# PQ60_CB_FV2.net
KiCad netlist of a schematic drawn in EAGLE
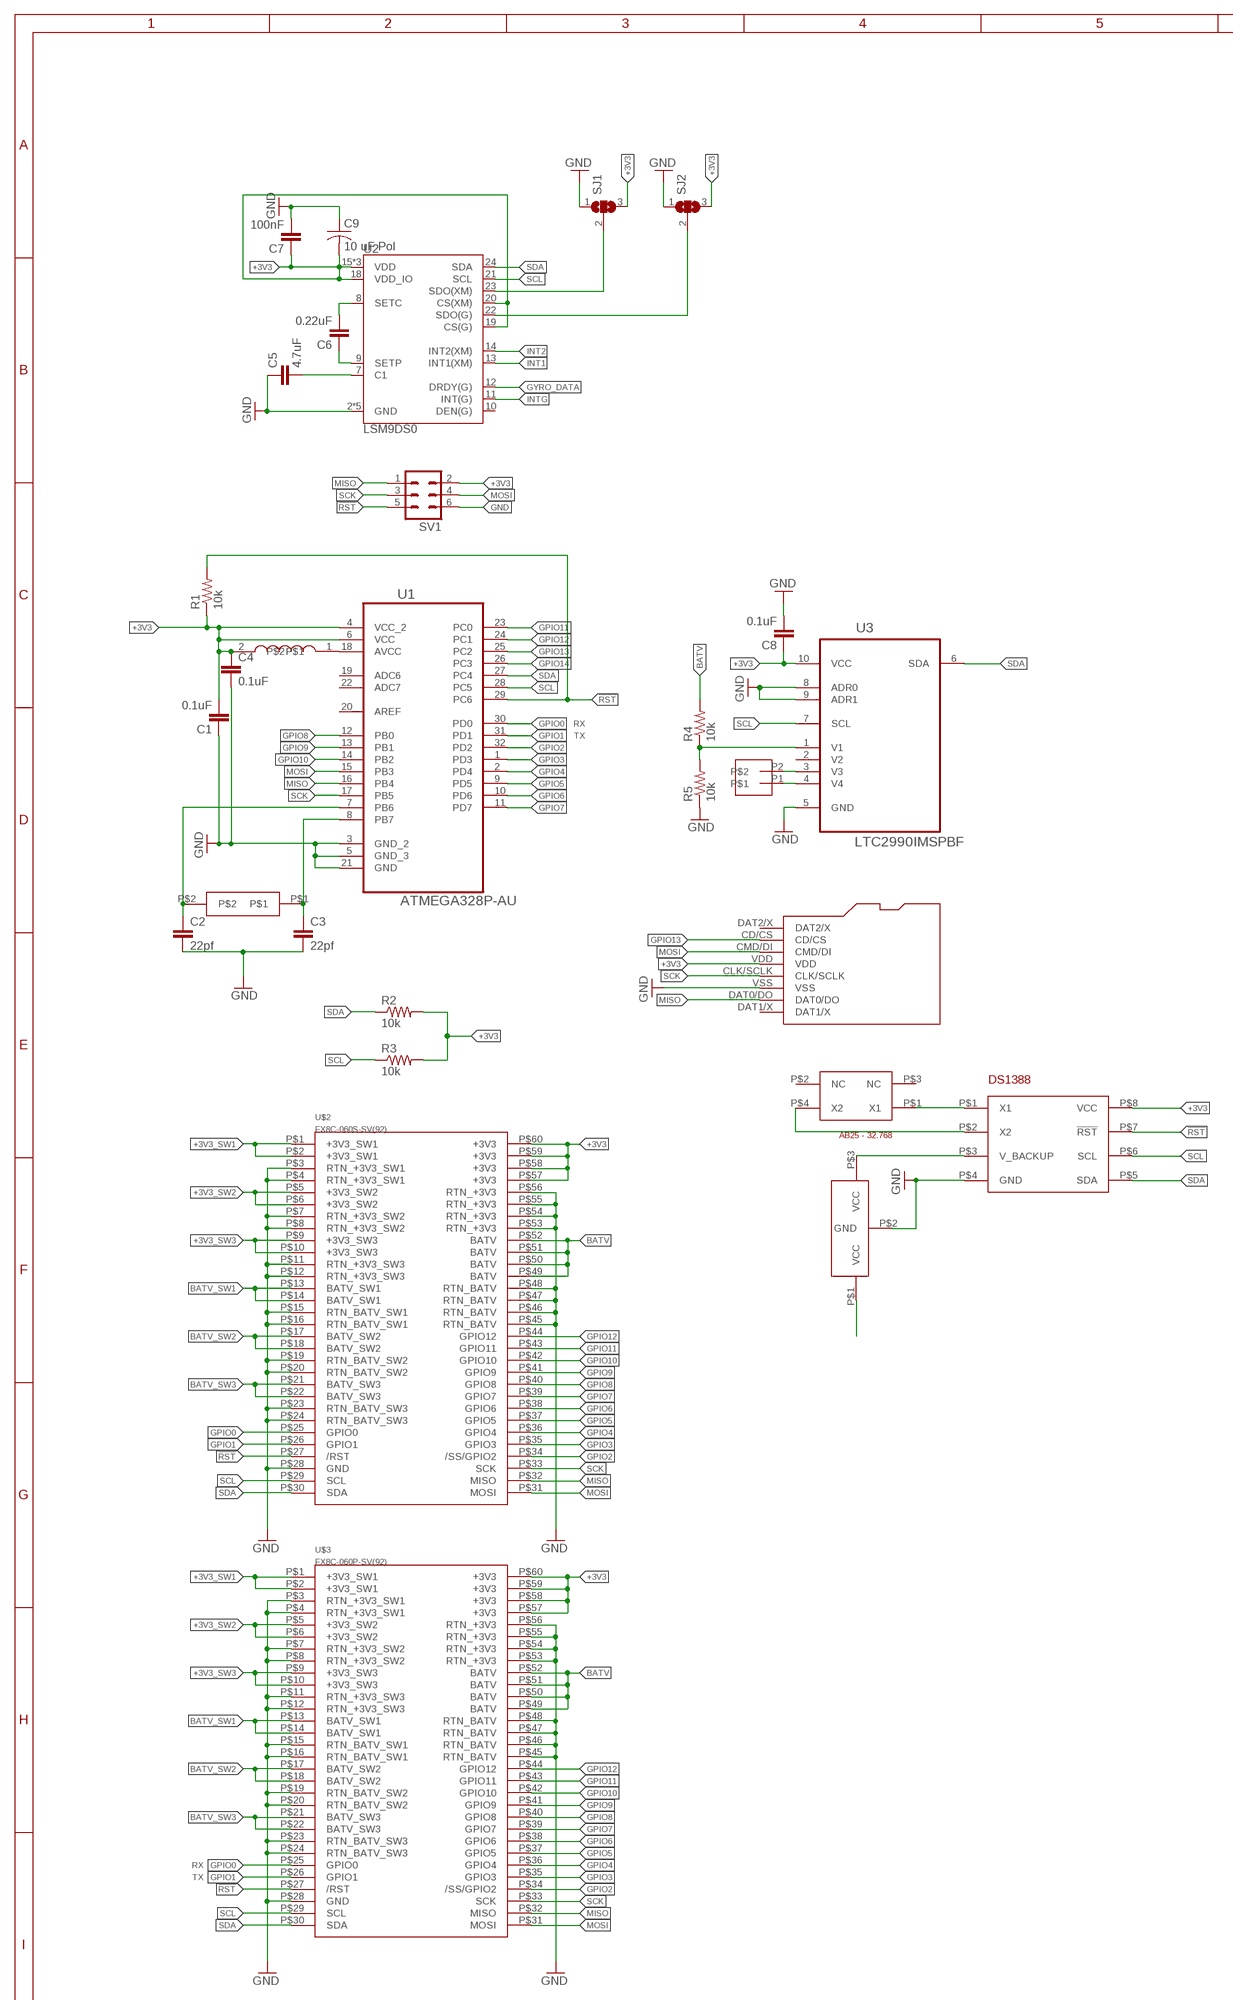
[diagram p0: schematic, sheet 1, part 1 of 2]
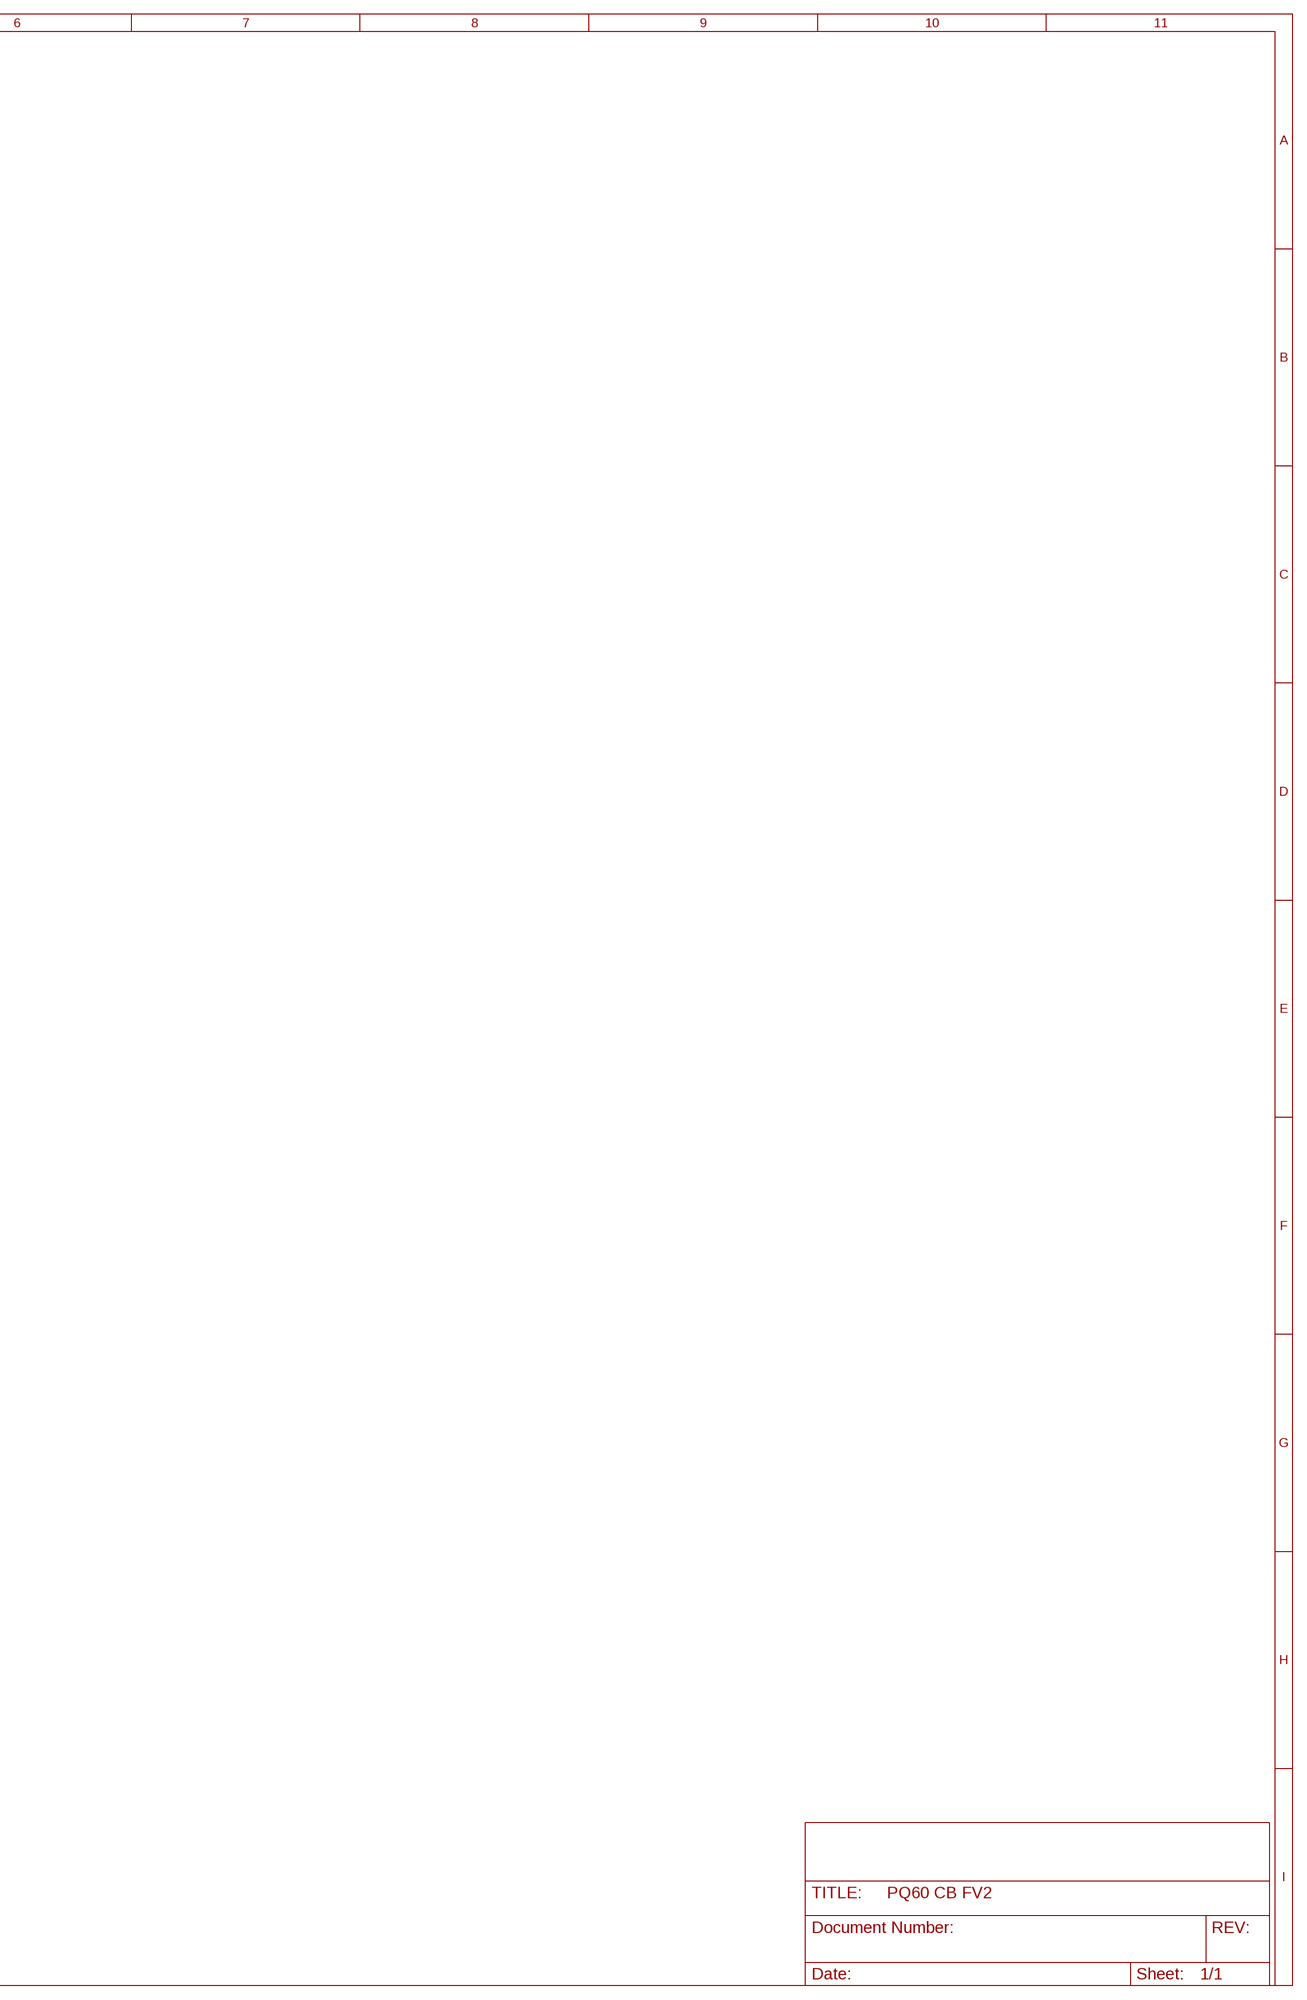
[diagram p1: schematic, sheet 1, part 2 of 2]

(export (version "E")
  (design (tool "Eeschema 10.0.6"))
  (components
    (comp (ref "C1")
      (value "0.1uF")
      (footprint "eagle-import:C0805")
      (libsource (lib "eagle-import") (part "resistor_C-EUC0805"))
    )
    (comp (ref "C2")
      (value "22pf")
      (footprint "eagle-import:C0805")
      (libsource (lib "eagle-import") (part "resistor_C-EUC0805"))
    )
    (comp (ref "C3")
      (value "22pf")
      (footprint "eagle-import:C0805")
      (libsource (lib "eagle-import") (part "resistor_C-EUC0805"))
    )
    (comp (ref "C4")
      (value "0.1uF")
      (footprint "eagle-import:C0805")
      (libsource (lib "eagle-import") (part "resistor_C-EUC0805"))
    )
    (comp (ref "C5")
      (value "4.7uF")
      (footprint "eagle-import:C0805")
      (libsource (lib "eagle-import") (part "C-EUC0805"))
    )
    (comp (ref "C6")
      (value "0.22uF")
      (footprint "eagle-import:C0805")
      (libsource (lib "eagle-import") (part "C-EUC0805"))
    )
    (comp (ref "C7")
      (value "100nF")
      (footprint "eagle-import:C0805")
      (libsource (lib "eagle-import") (part "C-EUC0805"))
    )
    (comp (ref "C8")
      (value "0.1uF")
      (footprint "eagle-import:C0805")
      (libsource (lib "eagle-import") (part "C-EUC0805"))
    )
    (comp (ref "C9")
      (value "10 uF Pol")
      (footprint "eagle-import:C0805")
      (libsource (lib "eagle-import") (part "C-USC0805"))
    )
    (comp (ref "R1")
      (value "10k")
      (footprint "eagle-import:R0805")
      (libsource (lib "eagle-import") (part "R-US_R0805"))
    )
    (comp (ref "R2")
      (value "10k")
      (footprint "eagle-import:M0805")
      (libsource (lib "eagle-import") (part "R-US_M0805"))
    )
    (comp (ref "R3")
      (value "10k")
      (footprint "eagle-import:M0805")
      (libsource (lib "eagle-import") (part "R-US_M0805"))
    )
    (comp (ref "R4")
      (value "10k")
      (footprint "eagle-import:M0805")
      (libsource (lib "eagle-import") (part "resistor_R-US_M0805"))
    )
    (comp (ref "R5")
      (value "10k")
      (footprint "eagle-import:M0805")
      (libsource (lib "eagle-import") (part "resistor_R-US_M0805"))
    )
    (comp (ref "SJ1")
      (value "SJ2W")
      (footprint "eagle-import:SJ_2")
      (libsource (lib "eagle-import") (part "SJ2W"))
    )
    (comp (ref "SJ2")
      (value "SJ2W")
      (footprint "eagle-import:SJ_2")
      (libsource (lib "eagle-import") (part "SJ2W"))
    )
    (comp (ref "SV1")
      (value "MA03-2")
      (footprint "eagle-import:MA03-2")
      (libsource (lib "eagle-import") (part "MA03-2"))
    )
    (comp (ref "U$2")
      (value "FX8C-060S-SV(92)")
      (footprint "eagle-import:FX8C-060S-SV(92)")
      (libsource (lib "eagle-import") (part "FX8C-060S-SV(92)"))
    )
    (comp (ref "U$3")
      (value "FX8C-060P-SV(92)")
      (footprint "eagle-import:FX8C-060P-SV(92)")
      (libsource (lib "eagle-import") (part "FX8C-060P-SV(92)"))
    )
    (comp (ref "U$4")
      (value "AB3-47699")
      (footprint "eagle-import:ABM#-47699")
      (libsource (lib "eagle-import") (part "AB3-47699"))
    )
    (comp (ref "U$5")
      (value "1210-047J")
      (footprint "eagle-import:1210-047J")
      (libsource (lib "eagle-import") (part "1210-047J"))
    )
    (comp (ref "U$6")
      (value "MICROSD")
      (footprint "eagle-import:MICROSD")
      (libsource (lib "eagle-import") (part "MICROSD"))
    )
    (comp (ref "U$7")
      (value "JST-SH-02")
      (footprint "eagle-import:JST-SH-02")
      (libsource (lib "eagle-import") (part "JST-SH-02"))
    )
    (comp (ref "U$8")
      (value "DS1388")
      (footprint "eagle-import:DS1388")
      (libsource (lib "eagle-import") (part "DS1388"))
    )
    (comp (ref "U$9")
      (value "AB25")
      (footprint "eagle-import:ABS25")
      (libsource (lib "eagle-import") (part "AB25"))
    )
    (comp (ref "U$10")
      (value "6.8MM-BATTERY")
      (footprint "eagle-import:6.8MM-BATTERY")
      (libsource (lib "eagle-import") (part "6.8MM-BATTERY"))
    )
    (comp (ref "U1")
      (value "ATMEGA328P-AU")
      (footprint "eagle-import:QFP80P900X900X120-32N")
      (libsource (lib "eagle-import") (part "ATMEGA328P-AU"))
    )
    (comp (ref "U2")
      (value "LSM9DS0")
      (footprint "eagle-import:LGA-24")
      (libsource (lib "eagle-import") (part "LSM9DS0"))
    )
    (comp (ref "U3")
      (value "LTC2990IMSPBF")
      (footprint "eagle-import:SOP50P490X110-10N")
      (fields (field (name "MPN") "LTC2990IMS#PBF"))
      (libsource (lib "eagle-import") (part "LTC2990IMSPBF"))
    )
  )
  (nets
    (net (code "1") (name "+3V3") (class "Default")
      (node (ref "C1") (pin "2") (pinfunction "2_2") (pintype "passive"))
      (node (ref "C4") (pin "1") (pinfunction "1_1") (pintype "passive"))
      (node (ref "C7") (pin "1") (pinfunction "1_1") (pintype "passive"))
      (node (ref "C8") (pin "1") (pinfunction "1_1") (pintype "passive"))
      (node (ref "C9") (pin "2") (pinfunction "2_2") (pintype "passive"))
      (node (ref "R1") (pin "1") (pinfunction "1_1") (pintype "passive"))
      (node (ref "R2") (pin "2") (pinfunction "2_2") (pintype "passive"))
      (node (ref "R3") (pin "2") (pinfunction "2_2") (pintype "passive"))
      (node (ref "SJ1") (pin "3") (pinfunction "3_3") (pintype "passive"))
      (node (ref "SJ2") (pin "3") (pinfunction "3_3") (pintype "passive"))
      (node (ref "SV1") (pin "2") (pinfunction "2_2") (pintype "passive"))
      (node (ref "U$2") (pin "P$57") (pinfunction "+3V3_P$57") (pintype "power_in"))
      (node (ref "U$2") (pin "P$58") (pinfunction "+3V3_P$58") (pintype "power_in"))
      (node (ref "U$2") (pin "P$59") (pinfunction "+3V3_P$59") (pintype "power_in"))
      (node (ref "U$2") (pin "P$60") (pinfunction "+3V3_P$60") (pintype "power_in"))
      (node (ref "U$3") (pin "P$57") (pinfunction "+3V3_P$57") (pintype "power_in"))
      (node (ref "U$3") (pin "P$58") (pinfunction "+3V3_P$58") (pintype "power_in"))
      (node (ref "U$3") (pin "P$59") (pinfunction "+3V3_P$59") (pintype "power_in"))
      (node (ref "U$3") (pin "P$60") (pinfunction "+3V3_P$60") (pintype "power_in"))
      (node (ref "U$5") (pin "2") (pinfunction "P$2_2") (pintype "bidirectional"))
      (node (ref "U$6") (pin "VDD") (pinfunction "VDD_VDD") (pintype "bidirectional"))
      (node (ref "U$8") (pin "P$8") (pinfunction "VCC_P$8") (pintype "power_in"))
      (node (ref "U1") (pin "4") (pinfunction "VCC_2_4") (pintype "power_in"))
      (node (ref "U1") (pin "6") (pinfunction "VCC_6") (pintype "power_in"))
      (node (ref "U2") (pin "15") (pinfunction "VDD_15") (pintype "bidirectional"))
      (node (ref "U2") (pin "16") (pinfunction "VDD_16") (pintype "bidirectional"))
      (node (ref "U2") (pin "17") (pinfunction "VDD_17") (pintype "bidirectional"))
      (node (ref "U2") (pin "18") (pinfunction "VDD_IO_18") (pintype "bidirectional"))
      (node (ref "U2") (pin "19") (pinfunction "CS(G)_19") (pintype "bidirectional"))
      (node (ref "U2") (pin "20") (pinfunction "CS(XM)_20") (pintype "bidirectional"))
      (node (ref "U3") (pin "10") (pinfunction "VCC_10") (pintype "power_in"))
    )
    (net (code "2") (name "+3V3_SW1") (class "Default")
      (node (ref "U$2") (pin "P$1") (pinfunction "+3V3_SW1_P$1") (pintype "power_in"))
      (node (ref "U$2") (pin "P$2") (pinfunction "+3V3_SW1_P$2") (pintype "power_in"))
      (node (ref "U$3") (pin "P$1") (pinfunction "+3V3_SW1_P$1") (pintype "power_in"))
      (node (ref "U$3") (pin "P$2") (pinfunction "+3V3_SW1_P$2") (pintype "power_in"))
    )
    (net (code "3") (name "+3V3_SW2") (class "Default")
      (node (ref "U$2") (pin "P$5") (pinfunction "+3V3_SW2_P$5") (pintype "power_in"))
      (node (ref "U$2") (pin "P$6") (pinfunction "+3V3_SW2_P$6") (pintype "power_in"))
      (node (ref "U$3") (pin "P$5") (pinfunction "+3V3_SW2_P$5") (pintype "power_in"))
      (node (ref "U$3") (pin "P$6") (pinfunction "+3V3_SW2_P$6") (pintype "power_in"))
    )
    (net (code "4") (name "+3V3_SW3") (class "Default")
      (node (ref "U$2") (pin "P$10") (pinfunction "+3V3_SW3_P$10") (pintype "power_in"))
      (node (ref "U$2") (pin "P$9") (pinfunction "+3V3_SW3_P$9") (pintype "power_in"))
      (node (ref "U$3") (pin "P$10") (pinfunction "+3V3_SW3_P$10") (pintype "power_in"))
      (node (ref "U$3") (pin "P$9") (pinfunction "+3V3_SW3_P$9") (pintype "power_in"))
    )
    (net (code "5") (name "/~{RST}") (class "Default")
      (node (ref "R1") (pin "2") (pinfunction "2_2") (pintype "passive"))
      (node (ref "SV1") (pin "5") (pinfunction "5_5") (pintype "passive"))
      (node (ref "U$2") (pin "P$27") (pinfunction "/RST_P$27") (pintype "bidirectional"))
      (node (ref "U$3") (pin "P$27") (pinfunction "/RST_P$27") (pintype "bidirectional"))
      (node (ref "U$8") (pin "P$7") (pinfunction "~{RST}_P$7") (pintype "output"))
      (node (ref "U1") (pin "29") (pinfunction "PC6_29") (pintype "bidirectional"))
    )
    (net (code "6") (name "BATV") (class "Default")
      (node (ref "R4") (pin "2") (pinfunction "2_2") (pintype "passive"))
      (node (ref "U$2") (pin "P$49") (pinfunction "BATV_P$49") (pintype "power_in"))
      (node (ref "U$2") (pin "P$50") (pinfunction "BATV_P$50") (pintype "power_in"))
      (node (ref "U$2") (pin "P$51") (pinfunction "BATV_P$51") (pintype "power_in"))
      (node (ref "U$2") (pin "P$52") (pinfunction "BATV_P$52") (pintype "power_in"))
      (node (ref "U$3") (pin "P$49") (pinfunction "BATV_P$49") (pintype "power_in"))
      (node (ref "U$3") (pin "P$50") (pinfunction "BATV_P$50") (pintype "power_in"))
      (node (ref "U$3") (pin "P$51") (pinfunction "BATV_P$51") (pintype "power_in"))
      (node (ref "U$3") (pin "P$52") (pinfunction "BATV_P$52") (pintype "power_in"))
    )
    (net (code "7") (name "BATV_SW1") (class "Default")
      (node (ref "U$2") (pin "P$13") (pinfunction "BATV_SW1_P$13") (pintype "power_in"))
      (node (ref "U$2") (pin "P$14") (pinfunction "BATV_SW1_P$14") (pintype "power_in"))
      (node (ref "U$3") (pin "P$13") (pinfunction "BATV_SW1_P$13") (pintype "power_in"))
      (node (ref "U$3") (pin "P$14") (pinfunction "BATV_SW1_P$14") (pintype "power_in"))
    )
    (net (code "8") (name "BATV_SW2") (class "Default")
      (node (ref "U$2") (pin "P$17") (pinfunction "BATV_SW2_P$17") (pintype "power_in"))
      (node (ref "U$2") (pin "P$18") (pinfunction "BATV_SW2_P$18") (pintype "power_in"))
      (node (ref "U$3") (pin "P$17") (pinfunction "BATV_SW2_P$17") (pintype "power_in"))
      (node (ref "U$3") (pin "P$18") (pinfunction "BATV_SW2_P$18") (pintype "power_in"))
    )
    (net (code "9") (name "BATV_SW3") (class "Default")
      (node (ref "U$2") (pin "P$21") (pinfunction "BATV_SW3_P$21") (pintype "power_in"))
      (node (ref "U$2") (pin "P$22") (pinfunction "BATV_SW3_P$22") (pintype "power_in"))
      (node (ref "U$3") (pin "P$21") (pinfunction "BATV_SW3_P$21") (pintype "power_in"))
      (node (ref "U$3") (pin "P$22") (pinfunction "BATV_SW3_P$22") (pintype "power_in"))
    )
    (net (code "10") (name "GND") (class "Default")
      (node (ref "C1") (pin "1") (pinfunction "1_1") (pintype "passive"))
      (node (ref "C2") (pin "2") (pinfunction "2_2") (pintype "passive"))
      (node (ref "C3") (pin "2") (pinfunction "2_2") (pintype "passive"))
      (node (ref "C4") (pin "2") (pinfunction "2_2") (pintype "passive"))
      (node (ref "C5") (pin "1") (pinfunction "1_1") (pintype "passive"))
      (node (ref "C7") (pin "2") (pinfunction "2_2") (pintype "passive"))
      (node (ref "C8") (pin "2") (pinfunction "2_2") (pintype "passive"))
      (node (ref "C9") (pin "1") (pinfunction "1_1") (pintype "passive"))
      (node (ref "R5") (pin "1") (pinfunction "1_1") (pintype "passive"))
      (node (ref "SJ1") (pin "1") (pinfunction "1_1") (pintype "passive"))
      (node (ref "SJ2") (pin "1") (pinfunction "1_1") (pintype "passive"))
      (node (ref "SV1") (pin "6") (pinfunction "6_6") (pintype "passive"))
      (node (ref "U$10") (pin "P$2") (pinfunction "GND_P$2") (pintype "power_in"))
      (node (ref "U$2") (pin "P$11") (pinfunction "RTN_+3V3_SW3_P$11") (pintype "power_in"))
      (node (ref "U$2") (pin "P$12") (pinfunction "RTN_+3V3_SW3_P$12") (pintype "power_in"))
      (node (ref "U$2") (pin "P$15") (pinfunction "RTN_BATV_SW1_P$15") (pintype "power_in"))
      (node (ref "U$2") (pin "P$16") (pinfunction "RTN_BATV_SW1_P$16") (pintype "power_in"))
      (node (ref "U$2") (pin "P$19") (pinfunction "RTN_BATV_SW2_P$19") (pintype "power_in"))
      (node (ref "U$2") (pin "P$20") (pinfunction "RTN_BATV_SW2_P$20") (pintype "power_in"))
      (node (ref "U$2") (pin "P$23") (pinfunction "RTN_BATV_SW3_P$23") (pintype "power_in"))
      (node (ref "U$2") (pin "P$24") (pinfunction "RTN_BATV_SW3_P$24") (pintype "power_in"))
      (node (ref "U$2") (pin "P$28") (pinfunction "GND_P$28") (pintype "bidirectional"))
      (node (ref "U$2") (pin "P$3") (pinfunction "RTN_+3V3_SW1_P$3") (pintype "power_in"))
      (node (ref "U$2") (pin "P$4") (pinfunction "RTN_+3V3_SW1_P$4") (pintype "power_in"))
      (node (ref "U$2") (pin "P$45") (pinfunction "RTN_BATV_P$45") (pintype "power_in"))
      (node (ref "U$2") (pin "P$46") (pinfunction "RTN_BATV_P$46") (pintype "power_in"))
      (node (ref "U$2") (pin "P$47") (pinfunction "RTN_BATV_P$47") (pintype "power_in"))
      (node (ref "U$2") (pin "P$48") (pinfunction "RTN_BATV_P$48") (pintype "power_in"))
      (node (ref "U$2") (pin "P$53") (pinfunction "RTN_+3V3_P$53") (pintype "power_in"))
      (node (ref "U$2") (pin "P$54") (pinfunction "RTN_+3V3_P$54") (pintype "power_in"))
      (node (ref "U$2") (pin "P$55") (pinfunction "RTN_+3V3_P$55") (pintype "power_in"))
      (node (ref "U$2") (pin "P$56") (pinfunction "RTN_+3V3_P$56") (pintype "power_in"))
      (node (ref "U$2") (pin "P$7") (pinfunction "RTN_+3V3_SW2_P$7") (pintype "power_in"))
      (node (ref "U$2") (pin "P$8") (pinfunction "RTN_+3V3_SW2_P$8") (pintype "power_in"))
      (node (ref "U$3") (pin "P$11") (pinfunction "RTN_+3V3_SW3_P$11") (pintype "power_in"))
      (node (ref "U$3") (pin "P$12") (pinfunction "RTN_+3V3_SW3_P$12") (pintype "power_in"))
      (node (ref "U$3") (pin "P$15") (pinfunction "RTN_BATV_SW1_P$15") (pintype "power_in"))
      (node (ref "U$3") (pin "P$16") (pinfunction "RTN_BATV_SW1_P$16") (pintype "power_in"))
      (node (ref "U$3") (pin "P$19") (pinfunction "RTN_BATV_SW2_P$19") (pintype "power_in"))
      (node (ref "U$3") (pin "P$20") (pinfunction "RTN_BATV_SW2_P$20") (pintype "power_in"))
      (node (ref "U$3") (pin "P$23") (pinfunction "RTN_BATV_SW3_P$23") (pintype "power_in"))
      (node (ref "U$3") (pin "P$24") (pinfunction "RTN_BATV_SW3_P$24") (pintype "power_in"))
      (node (ref "U$3") (pin "P$28") (pinfunction "GND_P$28") (pintype "bidirectional"))
      (node (ref "U$3") (pin "P$3") (pinfunction "RTN_+3V3_SW1_P$3") (pintype "power_in"))
      (node (ref "U$3") (pin "P$4") (pinfunction "RTN_+3V3_SW1_P$4") (pintype "power_in"))
      (node (ref "U$3") (pin "P$45") (pinfunction "RTN_BATV_P$45") (pintype "power_in"))
      (node (ref "U$3") (pin "P$46") (pinfunction "RTN_BATV_P$46") (pintype "power_in"))
      (node (ref "U$3") (pin "P$47") (pinfunction "RTN_BATV_P$47") (pintype "power_in"))
      (node (ref "U$3") (pin "P$48") (pinfunction "RTN_BATV_P$48") (pintype "power_in"))
      (node (ref "U$3") (pin "P$53") (pinfunction "RTN_+3V3_P$53") (pintype "power_in"))
      (node (ref "U$3") (pin "P$54") (pinfunction "RTN_+3V3_P$54") (pintype "power_in"))
      (node (ref "U$3") (pin "P$55") (pinfunction "RTN_+3V3_P$55") (pintype "power_in"))
      (node (ref "U$3") (pin "P$56") (pinfunction "RTN_+3V3_P$56") (pintype "power_in"))
      (node (ref "U$3") (pin "P$7") (pinfunction "RTN_+3V3_SW2_P$7") (pintype "power_in"))
      (node (ref "U$3") (pin "P$8") (pinfunction "RTN_+3V3_SW2_P$8") (pintype "power_in"))
      (node (ref "U$6") (pin "VSS") (pinfunction "VSS_VSS") (pintype "bidirectional"))
      (node (ref "U$8") (pin "P$4") (pinfunction "GND_P$4") (pintype "power_in"))
      (node (ref "U1") (pin "21") (pinfunction "GND_21") (pintype "passive"))
      (node (ref "U1") (pin "3") (pinfunction "GND_2_3") (pintype "passive"))
      (node (ref "U1") (pin "5") (pinfunction "GND_3_5") (pintype "passive"))
      (node (ref "U2") (pin "2") (pinfunction "GND_2") (pintype "bidirectional"))
      (node (ref "U2") (pin "3") (pinfunction "GND_3") (pintype "bidirectional"))
      (node (ref "U2") (pin "4") (pinfunction "GND_4") (pintype "bidirectional"))
      (node (ref "U2") (pin "5") (pinfunction "GND_5") (pintype "bidirectional"))
      (node (ref "U2") (pin "6") (pinfunction "GND_6") (pintype "bidirectional"))
      (node (ref "U3") (pin "5") (pinfunction "GND_5") (pintype "passive"))
      (node (ref "U3") (pin "8") (pinfunction "ADR0_8") (pintype "input"))
      (node (ref "U3") (pin "9") (pinfunction "ADR1_9") (pintype "input"))
    )
    (net (code "11") (name "GPIO0") (class "Default")
      (node (ref "U$2") (pin "P$25") (pinfunction "GPIO0_P$25") (pintype "bidirectional"))
      (node (ref "U$3") (pin "P$25") (pinfunction "GPIO0_P$25") (pintype "bidirectional"))
      (node (ref "U1") (pin "30") (pinfunction "PD0_30") (pintype "bidirectional"))
    )
    (net (code "12") (name "GPIO1") (class "Default")
      (node (ref "U$2") (pin "P$26") (pinfunction "GPIO1_P$26") (pintype "bidirectional"))
      (node (ref "U$3") (pin "P$26") (pinfunction "GPIO1_P$26") (pintype "bidirectional"))
      (node (ref "U1") (pin "31") (pinfunction "PD1_31") (pintype "bidirectional"))
    )
    (net (code "13") (name "GPIO2") (class "Default")
      (node (ref "U$2") (pin "P$34") (pinfunction "/SS/GPIO2_P$34") (pintype "bidirectional"))
      (node (ref "U$3") (pin "P$34") (pinfunction "/SS/GPIO2_P$34") (pintype "bidirectional"))
      (node (ref "U1") (pin "32") (pinfunction "PD2_32") (pintype "bidirectional"))
    )
    (net (code "14") (name "GPIO3") (class "Default")
      (node (ref "U$2") (pin "P$35") (pinfunction "GPIO3_P$35") (pintype "bidirectional"))
      (node (ref "U$3") (pin "P$35") (pinfunction "GPIO3_P$35") (pintype "bidirectional"))
      (node (ref "U1") (pin "1") (pinfunction "PD3_1") (pintype "bidirectional"))
    )
    (net (code "15") (name "GPIO4") (class "Default")
      (node (ref "U$2") (pin "P$36") (pinfunction "GPIO4_P$36") (pintype "bidirectional"))
      (node (ref "U$3") (pin "P$36") (pinfunction "GPIO4_P$36") (pintype "bidirectional"))
      (node (ref "U1") (pin "2") (pinfunction "PD4_2") (pintype "bidirectional"))
    )
    (net (code "16") (name "GPIO5") (class "Default")
      (node (ref "U$2") (pin "P$37") (pinfunction "GPIO5_P$37") (pintype "bidirectional"))
      (node (ref "U$3") (pin "P$37") (pinfunction "GPIO5_P$37") (pintype "bidirectional"))
      (node (ref "U1") (pin "9") (pinfunction "PD5_9") (pintype "bidirectional"))
    )
    (net (code "17") (name "GPIO6") (class "Default")
      (node (ref "U$2") (pin "P$38") (pinfunction "GPIO6_P$38") (pintype "bidirectional"))
      (node (ref "U$3") (pin "P$38") (pinfunction "GPIO6_P$38") (pintype "bidirectional"))
      (node (ref "U1") (pin "10") (pinfunction "PD6_10") (pintype "bidirectional"))
    )
    (net (code "18") (name "GPIO7") (class "Default")
      (node (ref "U$2") (pin "P$39") (pinfunction "GPIO7_P$39") (pintype "bidirectional"))
      (node (ref "U$3") (pin "P$39") (pinfunction "GPIO7_P$39") (pintype "bidirectional"))
      (node (ref "U1") (pin "11") (pinfunction "PD7_11") (pintype "bidirectional"))
    )
    (net (code "19") (name "GPIO8") (class "Default")
      (node (ref "U$2") (pin "P$40") (pinfunction "GPIO8_P$40") (pintype "bidirectional"))
      (node (ref "U$3") (pin "P$40") (pinfunction "GPIO8_P$40") (pintype "bidirectional"))
      (node (ref "U1") (pin "12") (pinfunction "PB0_12") (pintype "bidirectional"))
    )
    (net (code "20") (name "GPIO9") (class "Default")
      (node (ref "U$2") (pin "P$41") (pinfunction "GPIO9_P$41") (pintype "bidirectional"))
      (node (ref "U$3") (pin "P$41") (pinfunction "GPIO9_P$41") (pintype "bidirectional"))
      (node (ref "U1") (pin "13") (pinfunction "PB1_13") (pintype "bidirectional"))
    )
    (net (code "21") (name "GPIO10") (class "Default")
      (node (ref "U$2") (pin "P$42") (pinfunction "GPIO10_P$42") (pintype "bidirectional"))
      (node (ref "U$3") (pin "P$42") (pinfunction "GPIO10_P$42") (pintype "bidirectional"))
      (node (ref "U1") (pin "14") (pinfunction "PB2_14") (pintype "bidirectional"))
    )
    (net (code "22") (name "GPIO11") (class "Default")
      (node (ref "U$2") (pin "P$43") (pinfunction "GPIO11_P$43") (pintype "bidirectional"))
      (node (ref "U$3") (pin "P$43") (pinfunction "GPIO11_P$43") (pintype "bidirectional"))
      (node (ref "U1") (pin "23") (pinfunction "PC0_23") (pintype "bidirectional"))
    )
    (net (code "23") (name "GPIO12") (class "Default")
      (node (ref "U$2") (pin "P$44") (pinfunction "GPIO12_P$44") (pintype "bidirectional"))
      (node (ref "U$3") (pin "P$44") (pinfunction "GPIO12_P$44") (pintype "bidirectional"))
      (node (ref "U1") (pin "24") (pinfunction "PC1_24") (pintype "bidirectional"))
    )
    (net (code "24") (name "GPIO13") (class "Default")
      (node (ref "U$6") (pin "CD/CS") (pinfunction "CD/CS_CD/CS") (pintype "bidirectional"))
      (node (ref "U1") (pin "25") (pinfunction "PC2_25") (pintype "bidirectional"))
    )
    (net (code "25") (name "GPIO14") (class "Default")
      (node (ref "U1") (pin "26") (pinfunction "PC3_26") (pintype "bidirectional"))
    )
    (net (code "26") (name "GYRO_DATA") (class "Default")
      (node (ref "U2") (pin "12") (pinfunction "DRDY(G)_12") (pintype "bidirectional"))
    )
    (net (code "27") (name "INT1") (class "Default")
      (node (ref "U2") (pin "13") (pinfunction "INT1(XM)_13") (pintype "bidirectional"))
    )
    (net (code "28") (name "INT2") (class "Default")
      (node (ref "U2") (pin "14") (pinfunction "INT2(XM)_14") (pintype "bidirectional"))
    )
    (net (code "29") (name "INTG") (class "Default")
      (node (ref "U2") (pin "11") (pinfunction "INT(G)_11") (pintype "bidirectional"))
    )
    (net (code "30") (name "MISO") (class "Default")
      (node (ref "SV1") (pin "1") (pinfunction "1_1") (pintype "passive"))
      (node (ref "U$2") (pin "P$32") (pinfunction "MISO_P$32") (pintype "bidirectional"))
      (node (ref "U$3") (pin "P$32") (pinfunction "MISO_P$32") (pintype "bidirectional"))
      (node (ref "U$6") (pin "DAT0/DO") (pinfunction "DAT0/DO_DAT0/DO") (pintype "bidirectional"))
      (node (ref "U1") (pin "16") (pinfunction "PB4_16") (pintype "bidirectional"))
    )
    (net (code "31") (name "MOSI") (class "Default")
      (node (ref "SV1") (pin "4") (pinfunction "4_4") (pintype "passive"))
      (node (ref "U$2") (pin "P$31") (pinfunction "MOSI_P$31") (pintype "bidirectional"))
      (node (ref "U$3") (pin "P$31") (pinfunction "MOSI_P$31") (pintype "bidirectional"))
      (node (ref "U$6") (pin "CMD/DI") (pinfunction "CMD/DI_CMD/DI") (pintype "bidirectional"))
      (node (ref "U1") (pin "15") (pinfunction "PB3_15") (pintype "bidirectional"))
    )
    (net (code "32") (name "Net-(U$5-P$1)") (class "Default")
      (node (ref "U$5") (pin "1") (pinfunction "P$1_1") (pintype "bidirectional"))
      (node (ref "U1") (pin "18") (pinfunction "AVCC_18") (pintype "power_in"))
    )
    (net (code "33") (name "Net-(U$7-P$1)") (class "Default")
      (node (ref "U$7") (pin "P1") (pinfunction "P$1_P1") (pintype "bidirectional"))
      (node (ref "U3") (pin "4") (pinfunction "V4_4") (pintype "input"))
    )
    (net (code "34") (name "Net-(U$7-P$2)") (class "Default")
      (node (ref "U$7") (pin "P2") (pinfunction "P$2_P2") (pintype "bidirectional"))
      (node (ref "U3") (pin "3") (pinfunction "V3_3") (pintype "input"))
    )
    (net (code "35") (name "Net-(U$8-V_BACKUP)") (class "Default")
      (node (ref "U$10") (pin "P$3") (pinfunction "VCC_P$3") (pintype "power_in"))
      (node (ref "U$8") (pin "P$3") (pinfunction "V_BACKUP_P$3") (pintype "power_in"))
    )
    (net (code "36") (name "Net-(U$8-X1)") (class "Default")
      (node (ref "U$8") (pin "P$1") (pinfunction "X1_P$1") (pintype "input"))
      (node (ref "U$9") (pin "P$1") (pinfunction "X1_P$1") (pintype "bidirectional"))
    )
    (net (code "37") (name "Net-(U$8-X2)") (class "Default")
      (node (ref "U$8") (pin "P$2") (pinfunction "X2_P$2") (pintype "input"))
      (node (ref "U$9") (pin "P$4") (pinfunction "X2_P$4") (pintype "bidirectional"))
    )
    (net (code "38") (name "Net-(U1-PB6)") (class "Default")
      (node (ref "C2") (pin "1") (pinfunction "1_1") (pintype "passive"))
      (node (ref "U$4") (pin "P$2") (pinfunction "P$2_P$2") (pintype "bidirectional"))
      (node (ref "U1") (pin "7") (pinfunction "PB6_7") (pintype "bidirectional"))
    )
    (net (code "39") (name "Net-(U1-PB7)") (class "Default")
      (node (ref "C3") (pin "1") (pinfunction "1_1") (pintype "passive"))
      (node (ref "U$4") (pin "P$1") (pinfunction "P$1_P$1") (pintype "bidirectional"))
      (node (ref "U1") (pin "8") (pinfunction "PB7_8") (pintype "bidirectional"))
    )
    (net (code "40") (name "Net-(U2-C1)") (class "Default")
      (node (ref "C5") (pin "2") (pinfunction "2_2") (pintype "passive"))
      (node (ref "U2") (pin "7") (pinfunction "C1_7") (pintype "bidirectional"))
    )
    (net (code "41") (name "Net-(U2-SDO(G))") (class "Default")
      (node (ref "SJ2") (pin "2") (pinfunction "2_2") (pintype "passive"))
      (node (ref "U2") (pin "22") (pinfunction "SDO(G)_22") (pintype "bidirectional"))
    )
    (net (code "42") (name "Net-(U2-SDO(XM))") (class "Default")
      (node (ref "SJ1") (pin "2") (pinfunction "2_2") (pintype "passive"))
      (node (ref "U2") (pin "23") (pinfunction "SDO(XM)_23") (pintype "bidirectional"))
    )
    (net (code "43") (name "Net-(U2-SETC)") (class "Default")
      (node (ref "C6") (pin "2") (pinfunction "2_2") (pintype "passive"))
      (node (ref "U2") (pin "8") (pinfunction "SETC_8") (pintype "bidirectional"))
    )
    (net (code "44") (name "Net-(U2-SETP)") (class "Default")
      (node (ref "C6") (pin "1") (pinfunction "1_1") (pintype "passive"))
      (node (ref "U2") (pin "9") (pinfunction "SETP_9") (pintype "bidirectional"))
    )
    (net (code "45") (name "Net-(U3-V1)") (class "Default")
      (node (ref "R4") (pin "1") (pinfunction "1_1") (pintype "passive"))
      (node (ref "R5") (pin "2") (pinfunction "2_2") (pintype "passive"))
      (node (ref "U3") (pin "1") (pinfunction "V1_1") (pintype "input"))
    )
    (net (code "46") (name "SCK") (class "Default")
      (node (ref "SV1") (pin "3") (pinfunction "3_3") (pintype "passive"))
      (node (ref "U$2") (pin "P$33") (pinfunction "SCK_P$33") (pintype "bidirectional"))
      (node (ref "U$3") (pin "P$33") (pinfunction "SCK_P$33") (pintype "bidirectional"))
      (node (ref "U$6") (pin "CLK/SCLK") (pinfunction "CLK/SCLK_CLK/SCLK") (pintype "bidirectional"))
      (node (ref "U1") (pin "17") (pinfunction "PB5_17") (pintype "bidirectional"))
    )
    (net (code "47") (name "SCL") (class "Default")
      (node (ref "R3") (pin "1") (pinfunction "1_1") (pintype "passive"))
      (node (ref "U$2") (pin "P$29") (pinfunction "SCL_P$29") (pintype "bidirectional"))
      (node (ref "U$3") (pin "P$29") (pinfunction "SCL_P$29") (pintype "bidirectional"))
      (node (ref "U$8") (pin "P$6") (pinfunction "SCL_P$6") (pintype "bidirectional"))
      (node (ref "U1") (pin "28") (pinfunction "PC5_28") (pintype "bidirectional"))
      (node (ref "U2") (pin "21") (pinfunction "SCL_21") (pintype "bidirectional"))
      (node (ref "U3") (pin "7") (pinfunction "SCL_7") (pintype "input"))
    )
    (net (code "48") (name "SDA") (class "Default")
      (node (ref "R2") (pin "1") (pinfunction "1_1") (pintype "passive"))
      (node (ref "U$2") (pin "P$30") (pinfunction "SDA_P$30") (pintype "bidirectional"))
      (node (ref "U$3") (pin "P$30") (pinfunction "SDA_P$30") (pintype "bidirectional"))
      (node (ref "U$8") (pin "P$5") (pinfunction "SDA_P$5") (pintype "bidirectional"))
      (node (ref "U1") (pin "27") (pinfunction "PC4_27") (pintype "bidirectional"))
      (node (ref "U2") (pin "24") (pinfunction "SDA_24") (pintype "bidirectional"))
      (node (ref "U3") (pin "6") (pinfunction "SDA_6") (pintype "bidirectional"))
    )
    (net (code "49") (name "unconnected-(U$6-PadDAT1{slash}X)") (class "Default")
      (node (ref "U$6") (pin "DAT1/X") (pinfunction "DAT1/X_DAT1/X") (pintype "bidirectional"))
    )
    (net (code "50") (name "unconnected-(U$6-PadDAT2{slash}X)") (class "Default")
      (node (ref "U$6") (pin "DAT2/X") (pinfunction "DAT2/X_DAT2/X") (pintype "bidirectional"))
    )
    (net (code "51") (name "unconnected-(U$9-NC-PadP$2)") (class "Default")
      (node (ref "U$9") (pin "P$2") (pinfunction "NC_P$2") (pintype "no_connect"))
    )
    (net (code "52") (name "unconnected-(U$9-NC-PadP$3)") (class "Default")
      (node (ref "U$9") (pin "P$3") (pinfunction "NC_P$3") (pintype "no_connect"))
    )
    (net (code "53") (name "unconnected-(U$10-VCC-PadP$1)") (class "Default")
      (node (ref "U$10") (pin "P$1") (pinfunction "VCC_P$1") (pintype "power_in"))
    )
    (net (code "54") (name "unconnected-(U1-ADC6-Pad19)") (class "Default")
      (node (ref "U1") (pin "19") (pinfunction "ADC6_19") (pintype "input"))
    )
    (net (code "55") (name "unconnected-(U1-ADC7-Pad22)") (class "Default")
      (node (ref "U1") (pin "22") (pinfunction "ADC7_22") (pintype "input"))
    )
    (net (code "56") (name "unconnected-(U1-AREF-Pad20)") (class "Default")
      (node (ref "U1") (pin "20") (pinfunction "AREF_20") (pintype "input"))
    )
    (net (code "57") (name "unconnected-(U2-DEN(G)-Pad10)") (class "Default")
      (node (ref "U2") (pin "10") (pinfunction "DEN(G)_10") (pintype "bidirectional"))
    )
    (net (code "58") (name "unconnected-(U3-V2-Pad2)") (class "Default")
      (node (ref "U3") (pin "2") (pinfunction "V2_2") (pintype "input"))
    )
  )
)
